# regulation.net
KiCad netlist of a schematic drawn in Altium Designer
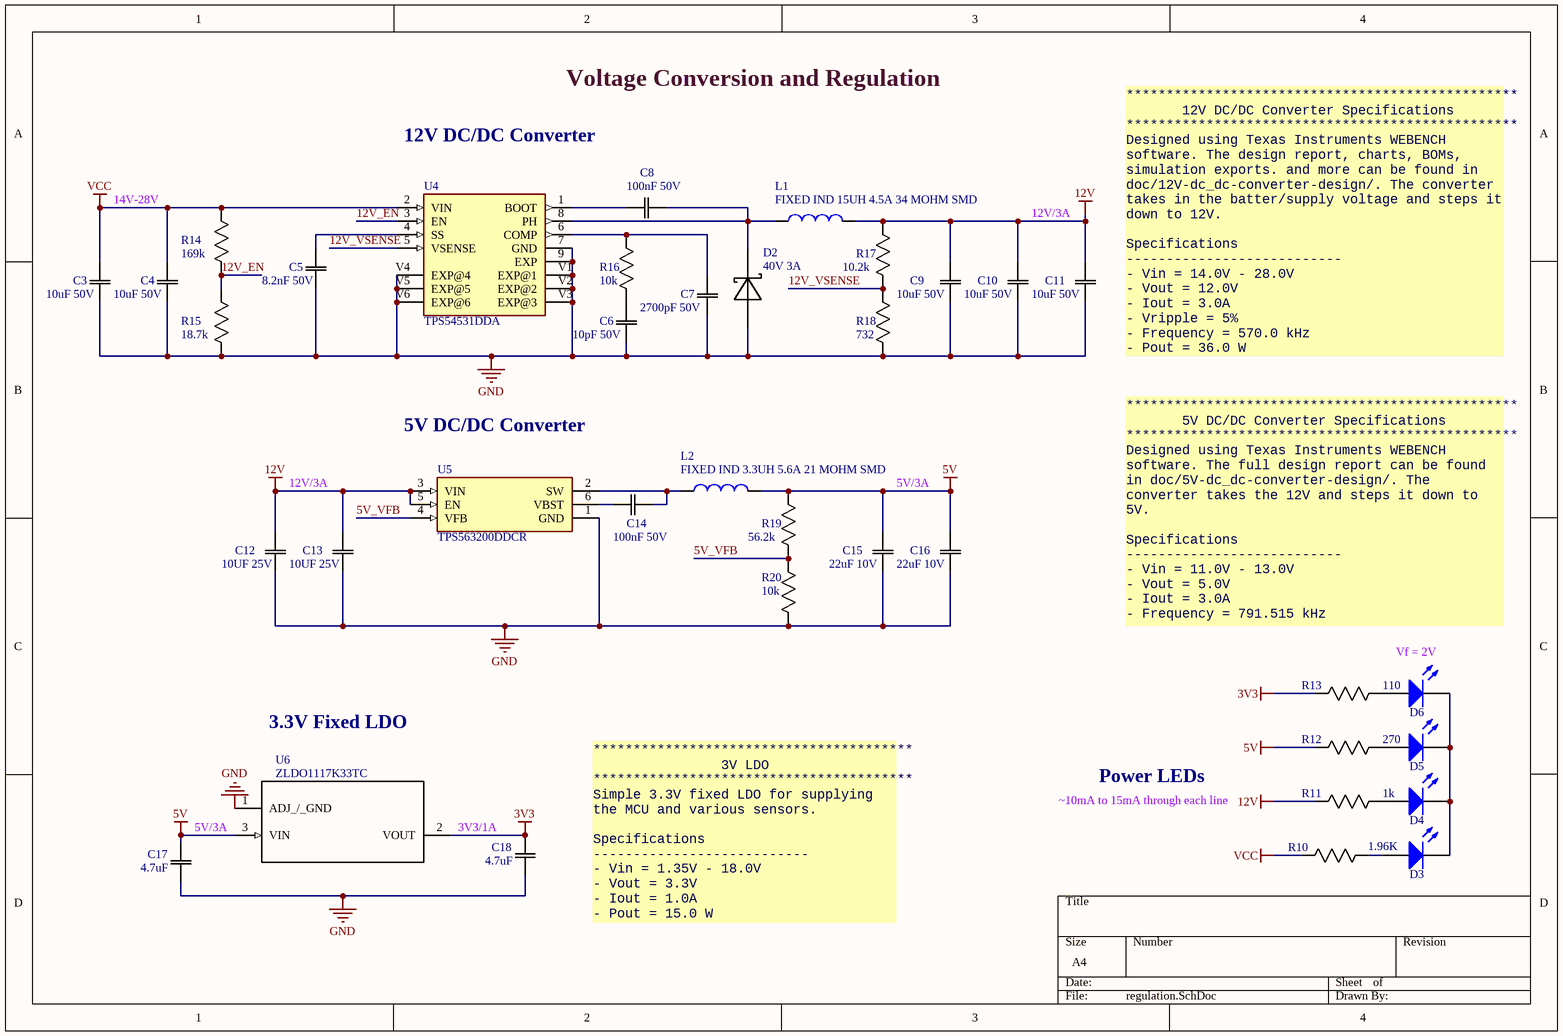
[diagram p0: regulation.SchDoc]

(export (version "E")
  (design (tool "Eeschema 10.0.6"))
  (components
    (comp (ref "C3")
      (value "10uF 50V")
      (footprint "1210")
      (description "CAP CER 10UF 50V X7R")
      (fields (field (name "TOLERANCE") "10%"))
      (libsource (lib "AltiumLibraries") (part "CAP 10uF 50V"))
    )
    (comp (ref "C4")
      (value "10uF 50V")
      (footprint "1210")
      (description "CAP CER 10UF 50V X7R")
      (fields (field (name "TOLERANCE") "10%"))
      (libsource (lib "AltiumLibraries") (part "CAP 10uF 50V"))
    )
    (comp (ref "C5")
      (value "8.2nF 50V")
      (footprint "0805")
      (description "CAP CER 8200PF 50V X7R 0805")
      (fields (field (name "TOLERANCE") "10%"))
      (libsource (lib "AltiumLibraries") (part "CAP 8.2nF 50V"))
    )
    (comp (ref "C6")
      (value "10pF 50V")
      (footprint "0603")
      (description "CAP CER 10PF 50V X7R 0603")
      (fields (field (name "TOLERANCE") "10%"))
      (libsource (lib "AltiumLibraries") (part "CAP 10pF 50V"))
    )
    (comp (ref "C7")
      (value "2700pF 50V")
      (footprint "0805")
      (description "CAP CER 2700PF 50V X7R 0805")
      (fields (field (name "TOLERANCE") "10%"))
      (libsource (lib "AltiumLibraries") (part "CAP 2700pF 50V"))
    )
    (comp (ref "C8")
      (value "100nF 50V")
      (footprint "0805")
      (description "CAP CER 0.1UF 50V X7R 0805")
      (fields (field (name "TOLERANCE") "10%"))
      (libsource (lib "AltiumLibraries") (part "CAP 100nF 50V"))
    )
    (comp (ref "C9")
      (value "10uF 50V")
      (footprint "1210")
      (description "CAP CER 10UF 50V X7R")
      (fields (field (name "TOLERANCE") "10%"))
      (libsource (lib "AltiumLibraries") (part "CAP 10uF 50V"))
    )
    (comp (ref "C10")
      (value "10uF 50V")
      (footprint "1210")
      (description "CAP CER 10UF 50V X7R")
      (fields (field (name "TOLERANCE") "10%"))
      (libsource (lib "AltiumLibraries") (part "CAP 10uF 50V"))
    )
    (comp (ref "C11")
      (value "10uF 50V")
      (footprint "1210")
      (description "CAP CER 10UF 50V X7R")
      (fields (field (name "TOLERANCE") "10%"))
      (libsource (lib "AltiumLibraries") (part "CAP 10uF 50V"))
    )
    (comp (ref "C12")
      (value "10UF 25V")
      (footprint "1206")
      (description "CAP CER 10UF 25V X5R 1206")
      (fields (field (name "TOLERANCE") "10%"))
      (libsource (lib "AltiumLibraries") (part "CAP 10uF 25V"))
    )
    (comp (ref "C13")
      (value "10UF 25V")
      (footprint "1206")
      (description "CAP CER 10UF 25V X5R 1206")
      (fields (field (name "TOLERANCE") "10%"))
      (libsource (lib "AltiumLibraries") (part "CAP 10uF 25V"))
    )
    (comp (ref "C14")
      (value "100nF 50V")
      (footprint "0805")
      (description "CAP CER 0.1UF 50V X7R 0805")
      (fields (field (name "TOLERANCE") "10%"))
      (libsource (lib "AltiumLibraries") (part "CAP 100nF 50V"))
    )
    (comp (ref "C15")
      (value "22uF 10V")
      (footprint "0805")
      (description "CAP CER 2.2UF 10V X5R 0805")
      (fields (field (name "TOLERANCE") "20%"))
      (libsource (lib "AltiumLibraries") (part "CAP 22uF 10V"))
    )
    (comp (ref "C16")
      (value "22uF 10V")
      (footprint "0805")
      (description "CAP CER 2.2UF 10V X5R 0805")
      (fields (field (name "TOLERANCE") "20%"))
      (libsource (lib "AltiumLibraries") (part "CAP 22uF 10V"))
    )
    (comp (ref "C17")
      (value "4.7uF")
      (footprint "0805")
      (description "CAP CER 4.7UF 25V X5R 0805")
      (fields (field (name "MP") "CL21B475KOFNNNE") (field (name "MF") "Samsung Electro-Mechanics"))
      (libsource (lib "AltiumLibraries") (part "CAP 4.7uF 0805"))
    )
    (comp (ref "C18")
      (value "4.7uF")
      (footprint "0805")
      (description "CAP CER 4.7UF 25V X5R 0805")
      (fields (field (name "MP") "CL21B475KOFNNNE") (field (name "MF") "Samsung Electro-Mechanics"))
      (libsource (lib "AltiumLibraries") (part "CAP 4.7uF 0805"))
    )
    (comp (ref "D2")
      (value "40V 3A")
      (footprint "DO-214AC")
      (description "Diode Schottky 40V 3A Surface Mount SMA")
      (libsource (lib "AltiumLibraries") (part "DIODE SCHOTTKY 40V 3A"))
    )
    (comp (ref "D3")
      (value "LED2")
      (footprint "3.2X1.6X1.1")
      (description "Typical RED, GREEN, YELLOW, AMBER GaAs LED")
      (libsource (lib "AltiumLibraries") (part "LED GREEN SMD"))
    )
    (comp (ref "D4")
      (value "LED2")
      (footprint "3.2X1.6X1.1")
      (description "Typical RED, GREEN, YELLOW, AMBER GaAs LED")
      (libsource (lib "AltiumLibraries") (part "LED GREEN SMD"))
    )
    (comp (ref "D5")
      (value "LED2")
      (footprint "3.2X1.6X1.1")
      (description "Typical RED, GREEN, YELLOW, AMBER GaAs LED")
      (libsource (lib "AltiumLibraries") (part "LED GREEN SMD"))
    )
    (comp (ref "D6")
      (value "LED2")
      (footprint "3.2X1.6X1.1")
      (description "Typical RED, GREEN, YELLOW, AMBER GaAs LED")
      (libsource (lib "AltiumLibraries") (part "LED GREEN SMD"))
    )
    (comp (ref "L1")
      (value "FIXED IND 15UH 4.5A 34 MOHM SMD")
      (description "15µH Unshielded Wirewound Inductor 4.5A 34mOhm Max Nonstandard")
      (fields (field (name "MP") "SDR1307-150ML") (field (name "MF") "Bourns Inc."))
      (libsource (lib "AltiumLibraries") (part "SDR1307-150ML"))
    )
    (comp (ref "L2")
      (value "FIXED IND 3.3UH 5.6A 21 MOHM SMD")
      (description "3.3µH Semi-Shielded Wirewound Inductor 5.6A 21mOhm Max Nonstandard")
      (fields (field (name "MP") "SRN8040-3R3Y") (field (name "MF") "Bourns Inc."))
      (libsource (lib "AltiumLibraries") (part "SRN8040-3R3Y"))
    )
    (comp (ref "R10")
      (value "1.96K")
      (footprint "0805")
      (description "RES SMD 1.96K OHM 1% 1/8W 0805")
      (fields (field (name "TOLERANCE") "1%"))
      (libsource (lib "AltiumLibraries") (part "RES 1.96k 1/8W"))
    )
    (comp (ref "R11")
      (value "1k")
      (footprint "0805")
      (description "RES SMD 1K OHM 5% 1/8W 0805")
      (fields (field (name "TOLERANCE") "5%"))
      (libsource (lib "AltiumLibraries") (part "RES 1k 1/8W"))
    )
    (comp (ref "R12")
      (value "270")
      (footprint "0805")
      (description "RES SMD 270 OHM 5% 1/8W 0805")
      (fields (field (name "TOLERANCE") "5%"))
      (libsource (lib "AltiumLibraries") (part "RES 270 1/8W"))
    )
    (comp (ref "R13")
      (value "110")
      (footprint "0805")
      (description "RES SMD 110 OHM 1% 1/8W 0805")
      (fields (field (name "TOLERANCE") "1%"))
      (libsource (lib "AltiumLibraries") (part "RES 110 1/8W"))
    )
    (comp (ref "R14")
      (value "169k")
      (footprint "0805")
      (description "RES SMD 169K OHM 1% 1/8W 0805")
      (fields (field (name "TOLERANCE") "1%"))
      (libsource (lib "AltiumLibraries") (part "RES 169k 1/8W"))
    )
    (comp (ref "R15")
      (value "18.7k")
      (footprint "1206")
      (description "RES SMD 18.7K OHM 1% 1/8W")
      (fields (field (name "TOLERANCE") "1%"))
      (libsource (lib "AltiumLibraries") (part "RES 18.7K OHM 1/8W"))
    )
    (comp (ref "R16")
      (value "10k")
      (footprint "0805")
      (description "RES SMD 10K OHM 1% 1/8W 0805")
      (fields (field (name "TOLERANCE") "1%"))
      (libsource (lib "AltiumLibraries") (part "RES 10k 1/8W"))
    )
    (comp (ref "R17")
      (value "10.2k")
      (footprint "0805")
      (description "RES SMD 10.2K OHM 1% 1/8W 0805")
      (fields (field (name "TOLERANCE") "1%"))
      (libsource (lib "AltiumLibraries") (part "RES 10.2k 1/8W"))
    )
    (comp (ref "R18")
      (value "732")
      (footprint "0805")
      (description "RES SMD 732 OHM 1% 1/8W 0805")
      (fields (field (name "TOLERANCE") "1%"))
      (libsource (lib "AltiumLibraries") (part "RES 732 1/8W"))
    )
    (comp (ref "R19")
      (value "56.2k")
      (footprint "0603")
      (description "RES SMD 56.2K OHM 1% 1/10W 0603")
      (fields (field (name "TOLERANCE") "1%"))
      (libsource (lib "AltiumLibraries") (part "RES 56.2k 1/10W"))
    )
    (comp (ref "R20")
      (value "10k")
      (footprint "0805")
      (description "RES SMD 10K OHM 1% 1/8W 0805")
      (fields (field (name "TOLERANCE") "1%"))
      (libsource (lib "AltiumLibraries") (part "RES 10k 1/8W"))
    )
    (comp (ref "U4")
      (value "TPS54531DDA")
      (footprint "8-PowerSOIC")
      (description "Buck Switching Regulator IC Positive Adjustable 0.8V 1 Output 5A 8-PowerSOIC _0.154, 3.90mm Width_")
      (fields (field (name "MF") "Texas Instruments"))
      (libsource (lib "AltiumLibraries") (part "TPS54531DDA"))
    )
    (comp (ref "U5")
      (value "TPS563200DDCR")
      (footprint "TSOT-23-6")
      (description "Buck Switching Regulator IC Positive Adjustable 0.76V 1 Output 3A SOT-23-6 Thin, TSOT-23-6")
      (fields (field (name "MF") "Texas Instruments"))
      (libsource (lib "AltiumLibraries") (part "TPS563200DDCR"))
    )
    (comp (ref "U6")
      (value "ZLDO1117K33TC")
      (footprint "TO-252-3")
      (description "Linear Voltage Regulator IC Positive Fixed 1 Output  1A TO-252-3")
      (fields (field (name "MF") "Diodes Incorporated"))
      (libsource (lib "AltiumLibraries") (part "ZLDO1117K33TC"))
    )
  )
  (nets
    (net (code "1") (name "/5V_VFB") (class "Default")
      (node (ref "R19") (pin "2") (pinfunction "R2_2") (pintype "passive"))
      (node (ref "R20") (pin "2") (pinfunction "R2_2") (pintype "passive"))
      (node (ref "U5") (pin "4") (pinfunction "VFB_4") (pintype "input"))
    )
    (net (code "2") (name "/12V_EN") (class "Default")
      (node (ref "R14") (pin "2") (pinfunction "R2_2") (pintype "passive"))
      (node (ref "R15") (pin "1") (pinfunction "R1_1") (pintype "passive"))
      (node (ref "U4") (pin "3") (pinfunction "EN_3") (pintype "input"))
    )
    (net (code "3") (name "/12V_VSENSE") (class "Default")
      (node (ref "R17") (pin "1") (pinfunction "R1_1") (pintype "passive"))
      (node (ref "R18") (pin "2") (pinfunction "R2_2") (pintype "passive"))
      (node (ref "U4") (pin "5") (pinfunction "VSENSE_5") (pintype "input"))
    )
    (net (code "4") (name "3V3") (class "Default")
      (node (ref "C18") (pin "2") (pinfunction "C2_2") (pintype "passive"))
      (node (ref "R13") (pin "1") (pinfunction "R1_1") (pintype "passive"))
      (node (ref "U6") (pin "2") (pinfunction "VOUT_2") (pintype "passive"))
    )
    (net (code "5") (name "5V") (class "Default")
      (node (ref "C15") (pin "2") (pinfunction "C2_2") (pintype "passive"))
      (node (ref "C16") (pin "2") (pinfunction "C2_2") (pintype "passive"))
      (node (ref "C17") (pin "2") (pinfunction "C2_2") (pintype "passive"))
      (node (ref "L2") (pin "2") (pinfunction "2_2") (pintype "passive"))
      (node (ref "R12") (pin "1") (pinfunction "R1_1") (pintype "passive"))
      (node (ref "R19") (pin "1") (pinfunction "R1_1") (pintype "passive"))
      (node (ref "U6") (pin "3") (pinfunction "VIN_3") (pintype "input"))
    )
    (net (code "6") (name "12V") (class "Default")
      (node (ref "C10") (pin "2") (pinfunction "C2_2") (pintype "passive"))
      (node (ref "C11") (pin "2") (pinfunction "C2_2") (pintype "passive"))
      (node (ref "C12") (pin "2") (pinfunction "C2_2") (pintype "passive"))
      (node (ref "C13") (pin "2") (pinfunction "C2_2") (pintype "passive"))
      (node (ref "C9") (pin "2") (pinfunction "C2_2") (pintype "passive"))
      (node (ref "L1") (pin "2") (pinfunction "2_2") (pintype "passive"))
      (node (ref "R11") (pin "1") (pinfunction "R1_1") (pintype "passive"))
      (node (ref "R17") (pin "2") (pinfunction "R2_2") (pintype "passive"))
      (node (ref "U5") (pin "3") (pinfunction "VIN_3") (pintype "input"))
      (node (ref "U5") (pin "5") (pinfunction "EN_5") (pintype "input"))
    )
    (net (code "7") (name "GND") (class "Default")
      (node (ref "C10") (pin "1") (pinfunction "C1_1") (pintype "passive"))
      (node (ref "C11") (pin "1") (pinfunction "C1_1") (pintype "passive"))
      (node (ref "C12") (pin "1") (pinfunction "C1_1") (pintype "passive"))
      (node (ref "C13") (pin "1") (pinfunction "C1_1") (pintype "passive"))
      (node (ref "C15") (pin "1") (pinfunction "C1_1") (pintype "passive"))
      (node (ref "C16") (pin "1") (pinfunction "C1_1") (pintype "passive"))
      (node (ref "C17") (pin "1") (pinfunction "C1_1") (pintype "passive"))
      (node (ref "C18") (pin "1") (pinfunction "C1_1") (pintype "passive"))
      (node (ref "C3") (pin "1") (pinfunction "C1_1") (pintype "passive"))
      (node (ref "C4") (pin "1") (pinfunction "C1_1") (pintype "passive"))
      (node (ref "C5") (pin "1") (pinfunction "C1_1") (pintype "passive"))
      (node (ref "C6") (pin "1") (pinfunction "C1_1") (pintype "passive"))
      (node (ref "C7") (pin "1") (pinfunction "C1_1") (pintype "passive"))
      (node (ref "C9") (pin "1") (pinfunction "C1_1") (pintype "passive"))
      (node (ref "D2") (pin "A") (pinfunction "A_A") (pintype "passive"))
      (node (ref "R15") (pin "2") (pinfunction "R2_2") (pintype "passive"))
      (node (ref "R18") (pin "1") (pinfunction "R1_1") (pintype "passive"))
      (node (ref "R20") (pin "1") (pinfunction "R1_1") (pintype "passive"))
      (node (ref "U4") (pin "7") (pinfunction "GND_7") (pintype "power_in"))
      (node (ref "U4") (pin "9") (pinfunction "EXP_9") (pintype "power_in"))
      (node (ref "U4") (pin "V1") (pinfunction "EXP@1_V1") (pintype "power_in"))
      (node (ref "U4") (pin "V2") (pinfunction "EXP@2_V2") (pintype "power_in"))
      (node (ref "U4") (pin "V3") (pinfunction "EXP@3_V3") (pintype "power_in"))
      (node (ref "U4") (pin "V4") (pinfunction "EXP@4_V4") (pintype "power_in"))
      (node (ref "U4") (pin "V5") (pinfunction "EXP@5_V5") (pintype "power_in"))
      (node (ref "U4") (pin "V6") (pinfunction "EXP@6_V6") (pintype "power_in"))
      (node (ref "U5") (pin "1") (pinfunction "GND_1") (pintype "power_in"))
      (node (ref "U6") (pin "1") (pinfunction "ADJ_/_GND_1") (pintype "power_in"))
    )
    (net (code "8") (name "Net-(C5-C2)") (class "Default")
      (node (ref "C5") (pin "2") (pinfunction "C2_2") (pintype "passive"))
      (node (ref "U4") (pin "4") (pinfunction "SS_4") (pintype "input"))
    )
    (net (code "9") (name "Net-(C6-C2)") (class "Default")
      (node (ref "C6") (pin "2") (pinfunction "C2_2") (pintype "passive"))
      (node (ref "R16") (pin "2") (pinfunction "R2_2") (pintype "passive"))
    )
    (net (code "10") (name "Net-(C7-C2)") (class "Default")
      (node (ref "C7") (pin "2") (pinfunction "C2_2") (pintype "passive"))
      (node (ref "R16") (pin "1") (pinfunction "R1_1") (pintype "passive"))
      (node (ref "U4") (pin "6") (pinfunction "COMP_6") (pintype "output"))
    )
    (net (code "11") (name "Net-(C8-C1)") (class "Default")
      (node (ref "C8") (pin "1") (pinfunction "C1_1") (pintype "passive"))
      (node (ref "U4") (pin "1") (pinfunction "BOOT_1") (pintype "output"))
    )
    (net (code "12") (name "Net-(C8-C2)") (class "Default")
      (node (ref "C8") (pin "2") (pinfunction "C2_2") (pintype "passive"))
      (node (ref "D2") (pin "C") (pinfunction "K_C") (pintype "passive"))
      (node (ref "L1") (pin "1") (pinfunction "1_1") (pintype "passive"))
      (node (ref "U4") (pin "8") (pinfunction "PH_8") (pintype "output"))
    )
    (net (code "13") (name "Net-(C14-C1)") (class "Default")
      (node (ref "C14") (pin "1") (pinfunction "C1_1") (pintype "passive"))
      (node (ref "U5") (pin "6") (pinfunction "VBST_6") (pintype "passive"))
    )
    (net (code "14") (name "Net-(C14-C2)") (class "Default")
      (node (ref "C14") (pin "2") (pinfunction "C2_2") (pintype "passive"))
      (node (ref "L2") (pin "1") (pinfunction "1_1") (pintype "passive"))
      (node (ref "U5") (pin "2") (pinfunction "SW_2") (pintype "passive"))
    )
    (net (code "15") (name "Net-(D3-A)") (class "Default")
      (node (ref "D3") (pin "1") (pinfunction "A_1") (pintype "passive"))
      (node (ref "R10") (pin "2") (pinfunction "R2_2") (pintype "passive"))
    )
    (net (code "16") (name "Net-(D3-K)") (class "Default")
      (node (ref "D3") (pin "2") (pinfunction "K_2") (pintype "passive"))
      (node (ref "D4") (pin "2") (pinfunction "K_2") (pintype "passive"))
      (node (ref "D5") (pin "2") (pinfunction "K_2") (pintype "passive"))
      (node (ref "D6") (pin "2") (pinfunction "K_2") (pintype "passive"))
    )
    (net (code "17") (name "Net-(D4-A)") (class "Default")
      (node (ref "D4") (pin "1") (pinfunction "A_1") (pintype "passive"))
      (node (ref "R11") (pin "2") (pinfunction "R2_2") (pintype "passive"))
    )
    (net (code "18") (name "Net-(D5-A)") (class "Default")
      (node (ref "D5") (pin "1") (pinfunction "A_1") (pintype "passive"))
      (node (ref "R12") (pin "2") (pinfunction "R2_2") (pintype "passive"))
    )
    (net (code "19") (name "Net-(D6-A)") (class "Default")
      (node (ref "D6") (pin "1") (pinfunction "A_1") (pintype "passive"))
      (node (ref "R13") (pin "2") (pinfunction "R2_2") (pintype "passive"))
    )
    (net (code "20") (name "VCC") (class "Default")
      (node (ref "C3") (pin "2") (pinfunction "C2_2") (pintype "passive"))
      (node (ref "C4") (pin "2") (pinfunction "C2_2") (pintype "passive"))
      (node (ref "R10") (pin "1") (pinfunction "R1_1") (pintype "passive"))
      (node (ref "R14") (pin "1") (pinfunction "R1_1") (pintype "passive"))
      (node (ref "U4") (pin "2") (pinfunction "VIN_2") (pintype "input"))
    )
  )
)
